# Schematic_Alarm_tone.net
KiCad netlist of a schematic drawn in Altium Designer
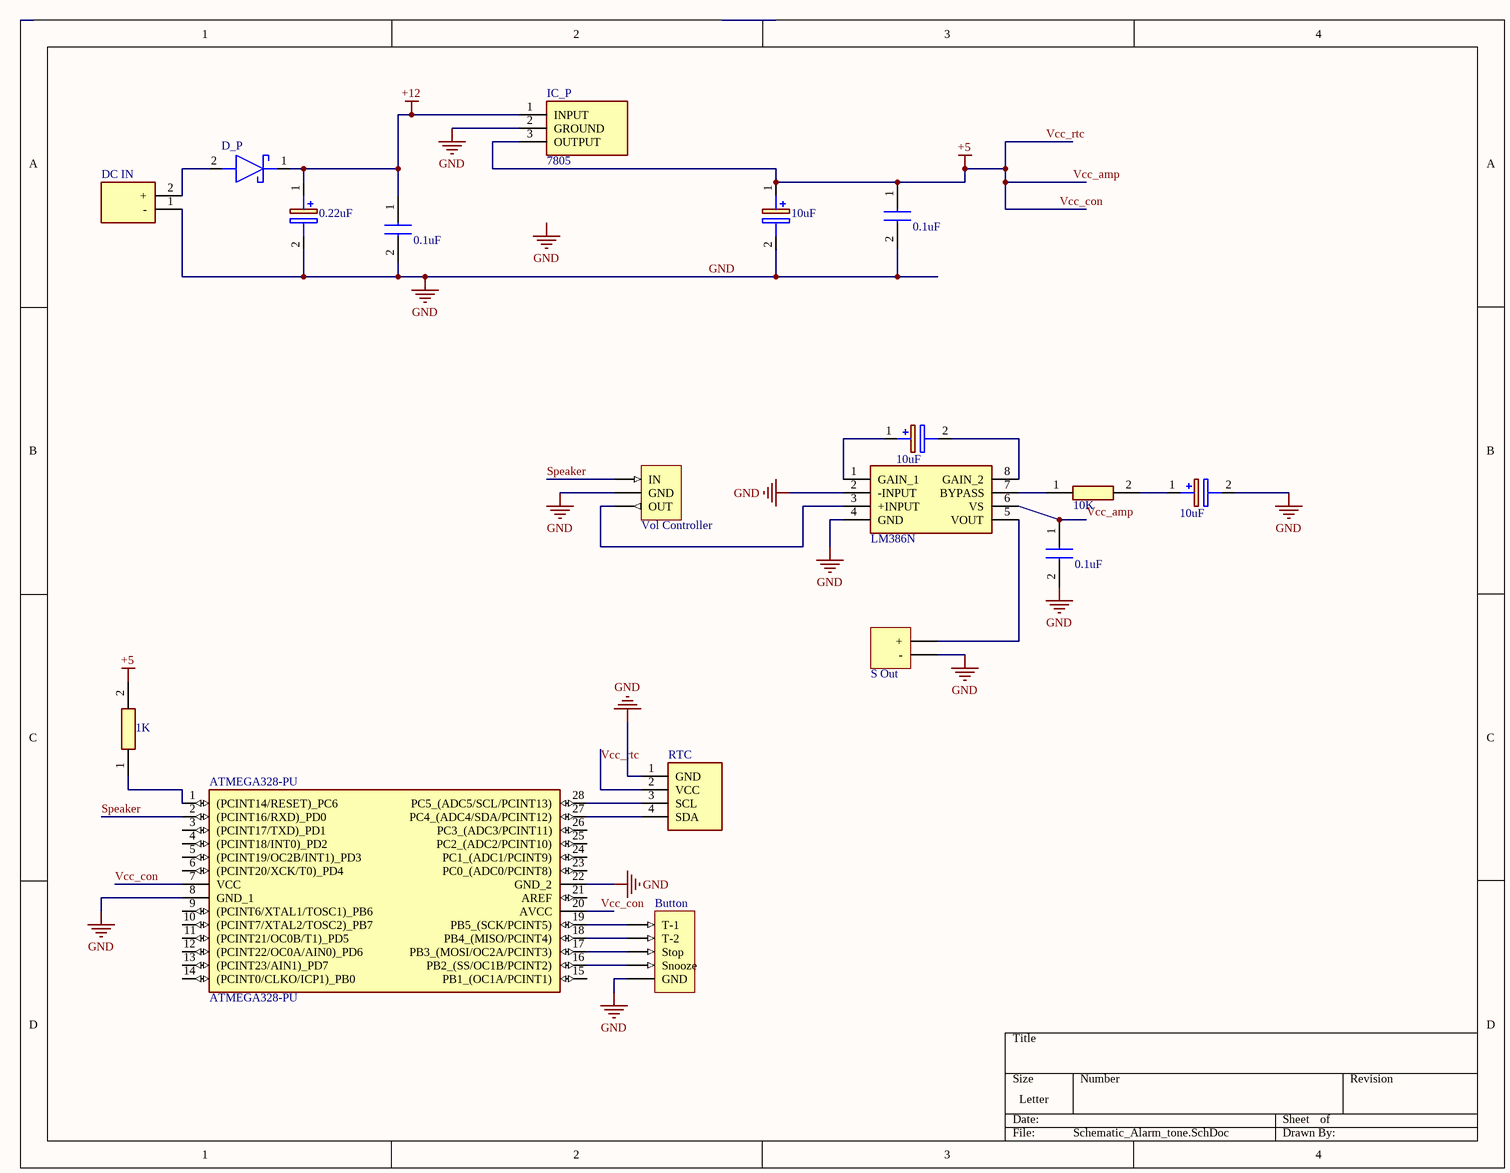
[diagram p0: Schematic_Alarm_tone.SchDoc]

(export (version "E")
  (design (tool "Eeschema 10.0.6"))
  (components
    (comp (ref "ATMEGA328-PU")
      (value "ATMEGA328-PU")
      (footprint "SamacSys:DIP1016W53P254L3468H457Q28N")
      (description "Integrated Circuit")
      (fields (field (name "MOUSER PART NUMBER") "556-ATMEGA328-PU"))
      (libsource (lib "*") (part "ATMEGA328-PU"))
    )
    (comp (ref "Button")
      (value "Header 5")
      (footprint "HDR1X5")
      (description "Header, 5-Pin")
      (fields (field (name "PUBLISHER") "Altium Limited"))
      (libsource (lib "Miscellaneous Connectors") (part "Header 5"))
    )
    (comp (ref "C1_A")
      (value "0.1uF")
      (footprint "SamacSys:RCE5C1H103J1A2H03B")
      (description "Capacitor")
      (fields (field (name "MANUFACTURER_PART_NUMBER") "RDER71E104K0K1H03B"))
      (libsource (lib "*") (part "RDER71E104K0K1H03B"))
    )
    (comp (ref "C1_P")
      (value "0.22uF")
      (footprint "SamacSys:CAPPRD200W52D500H1250")
      (description "Capacitor Polarised")
      (fields (field (name "MANUFACTURER_PART_NUMBER") "860010772002"))
      (libsource (lib "*") (part "860010772002"))
    )
    (comp (ref "C2_A")
      (value "10uF")
      (footprint "SamacSys:CAPPRD200W55D500H1250")
      (description "Capacitor Polarised")
      (fields
        (field (name "MOUSER2 PART NUMBER") "667-EEU-FR1H100")
        (field (name "MANUFACTURER_PART_NUMBER") "EEU-FR1H100")
      )
      (libsource (lib "") (part "EEU-FR1H100_1"))
    )
    (comp (ref "C2_P")
      (value "0.1uF")
      (footprint "SamacSys:RCE5C1H103J1A2H03B")
      (description "Capacitor")
      (fields (field (name "MANUFACTURER_PART_NUMBER") "RDER71E104K0K1H03B"))
      (libsource (lib "*") (part "RDER71E104K0K1H03B"))
    )
    (comp (ref "C3_A")
      (value "10uF")
      (footprint "SamacSys:CAPPRD200W55D500H1250")
      (description "Capacitor Polarised")
      (fields
        (field (name "MOUSER2 PART NUMBER") "667-EEU-FR1H100")
        (field (name "MANUFACTURER_PART_NUMBER") "EEU-FR1H100")
      )
      (libsource (lib "") (part "EEU-FR1H100_1"))
    )
    (comp (ref "C3_P")
      (value "10uF")
      (footprint "SamacSys:CAPPRD200W55D500H1250")
      (description "Capacitor Polarised")
      (fields
        (field (name "MOUSER2 PART NUMBER") "667-EEU-FR1H100")
        (field (name "MANUFACTURER_PART_NUMBER") "EEU-FR1H100")
      )
      (libsource (lib "*") (part "EEU-FR1H100"))
    )
    (comp (ref "C4_P")
      (value "0.1uF")
      (footprint "SamacSys:RCE5C1H103J1A2H03B")
      (description "Capacitor")
      (fields (field (name "MANUFACTURER_PART_NUMBER") "RDER71E104K0K1H03B"))
      (libsource (lib "*") (part "RDER71E104K0K1H03B"))
    )
    (comp (ref "DC IN")
      (value "0010845020")
      (footprint "SamacSys:0010845020")
      (description "Connector")
      (libsource (lib "*") (part "0010845020"))
    )
    (comp (ref "D_P")
      (value "SD103A-TR")
      (footprint "SamacSys:DIOAD950W60L350D150")
      (description "Schottky Diode")
      (fields (field (name "MOUSER2 PART NUMBER") "625-SD103A"))
      (libsource (lib "*") (part "SD103A-TR"))
    )
    (comp (ref "H4")
      (value "Vol Controller")
      (footprint "HDR1X3")
      (description "Header, 3-Pin")
      (fields (field (name "PUBLISHER") "Altium Limited"))
      (libsource (lib "Miscellaneous Connectors") (part "Header 3"))
    )
    (comp (ref "H5")
      (value "S Out")
      (footprint "HDR1X2")
      (description "Header, 2-Pin")
      (fields (field (name "PUBLISHER") "Altium Limited"))
      (libsource (lib "Miscellaneous Connectors") (part "Header 2"))
    )
    (comp (ref "IC")
      (value "LM386N")
      (footprint "SamacSys:DIP787W53P254L982H508Q8N")
      (description "Integrated Circuit")
      (fields
        (field (name "MANUFACTURER_PART_NUMBER") "LM386N-4")
        (field (name "MOUSER PART NUMBER") "926-LM386N-4")
      )
      (libsource (lib "*") (part "LM386N-4"))
    )
    (comp (ref "IC_P")
      (value "7805")
      (footprint "SamacSys:TO254P482X997X2018-3P")
      (description "Integrated Circuit")
      (fields
        (field (name "MANUFACTURER_PART_NUMBER") "MC7805CTG")
        (field (name "MOUSER PART NUMBER") "863-MC7805CTG")
      )
      (libsource (lib "*") (part "MC7805CTG"))
    )
    (comp (ref "R1_amp")
      (value "10K")
      (footprint "SamacSys:RESAD1650W60L650D250")
      (description "Resistor")
      (fields
        (field (name "MANUFACTURER_PART_NUMBER") "MRS25000C1002FRP00")
        (field (name "MOUSER PART NUMBER") "594-MRS2510K00F")
      )
      (libsource (lib "*") (part "MRS25000C1002FRP00"))
    )
    (comp (ref "R1_reset")
      (value "1K")
      (footprint "SamacSys:RESAD1680W59L680D250")
      (description "Resistor")
      (fields (field (name "MANUFACTURER_PART_NUMBER") "MF25 1K2"))
      (libsource (lib "*") (part "MF25_1K2"))
    )
    (comp (ref "RTC")
      (value "0022032041")
      (footprint "SamacSys:HDRV4W87P0X254_1X4_991X236X1155P")
      (description "Connector")
      (libsource (lib "*") (part "0022032041"))
    )
  )
  (nets
    (net (code "1") (name "+5") (class "Default")
      (node (ref "ATMEGA328-PU") (pin "20") (pinfunction "AVCC_20") (pintype "power_in"))
      (node (ref "ATMEGA328-PU") (pin "7") (pinfunction "VCC_7") (pintype "power_in"))
      (node (ref "C1_A") (pin "1") (pinfunction "1_1") (pintype "passive"))
      (node (ref "C3_P") (pin "1") (pinfunction "+_1") (pintype "power_in"))
      (node (ref "C4_P") (pin "1") (pinfunction "1_1") (pintype "passive"))
      (node (ref "IC") (pin "6") (pinfunction "VS_6") (pintype "passive"))
      (node (ref "IC_P") (pin "3") (pinfunction "OUTPUT_3") (pintype "power_in"))
      (node (ref "R1_reset") (pin "2") (pinfunction "2_2") (pintype "passive"))
      (node (ref "RTC") (pin "2") (pinfunction "VCC_2") (pintype "passive"))
    )
    (net (code "2") (name "+12") (class "Default")
      (node (ref "C1_P") (pin "1") (pinfunction "+_1") (pintype "passive"))
      (node (ref "C2_P") (pin "1") (pinfunction "1_1") (pintype "passive"))
      (node (ref "D_P") (pin "1") (pinfunction "K_1") (pintype "passive"))
      (node (ref "IC_P") (pin "1") (pinfunction "INPUT_1") (pintype "power_in"))
    )
    (net (code "4") (name "/Speaker") (class "Default")
      (node (ref "ATMEGA328-PU") (pin "2") (pinfunction "(PCINT16/RXD)_PD0_2") (pintype "bidirectional"))
      (node (ref "H4") (pin "1") (pinfunction "IN_1") (pintype "input"))
    )
    (net (code "5") (name "GND") (class "Default")
      (node (ref "ATMEGA328-PU") (pin "22") (pinfunction "GND_2_22") (pintype "power_in"))
      (node (ref "ATMEGA328-PU") (pin "8") (pinfunction "GND_1_8") (pintype "power_in"))
      (node (ref "Button") (pin "5") (pinfunction "GND_5") (pintype "power_in"))
      (node (ref "C1_A") (pin "2") (pinfunction "2_2") (pintype "passive"))
      (node (ref "C1_P") (pin "2") (pinfunction "-_2") (pintype "passive"))
      (node (ref "C2_P") (pin "2") (pinfunction "2_2") (pintype "passive"))
      (node (ref "C3_A") (pin "2") (pinfunction "-_2") (pintype "power_in"))
      (node (ref "C3_P") (pin "2") (pinfunction "-_2") (pintype "power_in"))
      (node (ref "C4_P") (pin "2") (pinfunction "2_2") (pintype "passive"))
      (node (ref "DC IN") (pin "1") (pinfunction "-_1") (pintype "power_in"))
      (node (ref "H4") (pin "2") (pinfunction "GND_2") (pintype "power_in"))
      (node (ref "H5") (pin "1") (pinfunction "-_1") (pintype "passive"))
      (node (ref "IC") (pin "2") (pinfunction "-INPUT_2") (pintype "passive"))
      (node (ref "IC") (pin "4") (pinfunction "GND_4") (pintype "passive"))
      (node (ref "IC_P") (pin "2") (pinfunction "GROUND_2") (pintype "power_in"))
      (node (ref "RTC") (pin "1") (pinfunction "GND_1") (pintype "passive"))
    )
    (net (code "6") (name "Net-(ATMEGA328-PU-(PCINT14{slash}RESET)_PC6)") (class "Default")
      (node (ref "ATMEGA328-PU") (pin "1") (pinfunction "(PCINT14/RESET)_PC6_1") (pintype "bidirectional"))
      (node (ref "R1_reset") (pin "1") (pinfunction "1_1") (pintype "passive"))
    )
    (net (code "7") (name "Net-(ATMEGA328-PU-PB2_(SS{slash}OC1B{slash}PCINT2))") (class "Default")
      (node (ref "ATMEGA328-PU") (pin "16") (pinfunction "PB2_(SS/OC1B/PCINT2)_16") (pintype "bidirectional"))
      (node (ref "Button") (pin "4") (pinfunction "Snooze_4") (pintype "input"))
    )
    (net (code "8") (name "Net-(ATMEGA328-PU-PB3_(MOSI{slash}OC2A{slash}PCINT3))") (class "Default")
      (node (ref "ATMEGA328-PU") (pin "17") (pinfunction "PB3_(MOSI/OC2A/PCINT3)_17") (pintype "bidirectional"))
      (node (ref "Button") (pin "3") (pinfunction "Stop_3") (pintype "input"))
    )
    (net (code "9") (name "Net-(ATMEGA328-PU-PB4_(MISO{slash}PCINT4))") (class "Default")
      (node (ref "ATMEGA328-PU") (pin "18") (pinfunction "PB4_(MISO/PCINT4)_18") (pintype "bidirectional"))
      (node (ref "Button") (pin "2") (pinfunction "T-2_2") (pintype "input"))
    )
    (net (code "10") (name "Net-(ATMEGA328-PU-PB5_(SCK{slash}PCINT5))") (class "Default")
      (node (ref "ATMEGA328-PU") (pin "19") (pinfunction "PB5_(SCK/PCINT5)_19") (pintype "bidirectional"))
      (node (ref "Button") (pin "1") (pinfunction "T-1_1") (pintype "input"))
    )
    (net (code "11") (name "Net-(ATMEGA328-PU-PC4_(ADC4{slash}SDA{slash}PCINT12))") (class "Default")
      (node (ref "ATMEGA328-PU") (pin "27") (pinfunction "PC4_(ADC4/SDA/PCINT12)_27") (pintype "bidirectional"))
      (node (ref "RTC") (pin "4") (pinfunction "SDA_4") (pintype "passive"))
    )
    (net (code "12") (name "Net-(ATMEGA328-PU-PC5_(ADC5{slash}SCL{slash}PCINT13))") (class "Default")
      (node (ref "ATMEGA328-PU") (pin "28") (pinfunction "PC5_(ADC5/SCL/PCINT13)_28") (pintype "bidirectional"))
      (node (ref "RTC") (pin "3") (pinfunction "SCL_3") (pintype "passive"))
    )
    (net (code "13") (name "Net-(C2_A-+)") (class "Default")
      (node (ref "C2_A") (pin "1") (pinfunction "+_1") (pintype "power_in"))
      (node (ref "IC") (pin "1") (pinfunction "GAIN_1_1") (pintype "passive"))
    )
    (net (code "14") (name "Net-(C2_A--)") (class "Default")
      (node (ref "C2_A") (pin "2") (pinfunction "-_2") (pintype "power_in"))
      (node (ref "IC") (pin "8") (pinfunction "GAIN_2_8") (pintype "passive"))
    )
    (net (code "15") (name "Net-(C3_A-+)") (class "Default")
      (node (ref "C3_A") (pin "1") (pinfunction "+_1") (pintype "power_in"))
      (node (ref "R1_amp") (pin "2") (pinfunction "2_2") (pintype "passive"))
    )
    (net (code "16") (name "Net-(DC IN-+)") (class "Default")
      (node (ref "DC IN") (pin "2") (pinfunction "+_2") (pintype "power_in"))
      (node (ref "D_P") (pin "2") (pinfunction "A_2") (pintype "passive"))
    )
    (net (code "17") (name "Net-(H4-OUT)") (class "Default")
      (node (ref "H4") (pin "3") (pinfunction "OUT_3") (pintype "output"))
      (node (ref "IC") (pin "3") (pinfunction "+INPUT_3") (pintype "passive"))
    )
    (net (code "18") (name "Net-(H5-+)") (class "Default")
      (node (ref "H5") (pin "2") (pinfunction "+_2") (pintype "passive"))
      (node (ref "IC") (pin "5") (pinfunction "VOUT_5") (pintype "passive"))
    )
    (net (code "19") (name "Net-(IC-BYPASS)") (class "Default")
      (node (ref "IC") (pin "7") (pinfunction "BYPASS_7") (pintype "passive"))
      (node (ref "R1_amp") (pin "1") (pinfunction "1_1") (pintype "passive"))
    )
    (net (code "20") (name "unconnected-(ATMEGA328-PU-(PCINT0{slash}CLKO{slash}ICP1)_PB0-Pad14)") (class "Default")
      (node (ref "ATMEGA328-PU") (pin "14") (pinfunction "(PCINT0/CLKO/ICP1)_PB0_14") (pintype "bidirectional"))
    )
    (net (code "21") (name "unconnected-(ATMEGA328-PU-(PCINT6{slash}XTAL1{slash}TOSC1)_PB6-Pad9)") (class "Default")
      (node (ref "ATMEGA328-PU") (pin "9") (pinfunction "(PCINT6/XTAL1/TOSC1)_PB6_9") (pintype "bidirectional"))
    )
    (net (code "22") (name "unconnected-(ATMEGA328-PU-(PCINT7{slash}XTAL2{slash}TOSC2)_PB7-Pad10)") (class "Default")
      (node (ref "ATMEGA328-PU") (pin "10") (pinfunction "(PCINT7/XTAL2/TOSC2)_PB7_10") (pintype "bidirectional"))
    )
    (net (code "23") (name "unconnected-(ATMEGA328-PU-(PCINT17{slash}TXD)_PD1-Pad3)") (class "Default")
      (node (ref "ATMEGA328-PU") (pin "3") (pinfunction "(PCINT17/TXD)_PD1_3") (pintype "bidirectional"))
    )
    (net (code "24") (name "unconnected-(ATMEGA328-PU-(PCINT18{slash}INT0)_PD2-Pad4)") (class "Default")
      (node (ref "ATMEGA328-PU") (pin "4") (pinfunction "(PCINT18/INT0)_PD2_4") (pintype "bidirectional"))
    )
    (net (code "25") (name "unconnected-(ATMEGA328-PU-(PCINT19{slash}OC2B{slash}INT1)_PD3-Pad5)") (class "Default")
      (node (ref "ATMEGA328-PU") (pin "5") (pinfunction "(PCINT19/OC2B/INT1)_PD3_5") (pintype "bidirectional"))
    )
    (net (code "26") (name "unconnected-(ATMEGA328-PU-(PCINT20{slash}XCK{slash}T0)_PD4-Pad6)") (class "Default")
      (node (ref "ATMEGA328-PU") (pin "6") (pinfunction "(PCINT20/XCK/T0)_PD4_6") (pintype "bidirectional"))
    )
    (net (code "27") (name "unconnected-(ATMEGA328-PU-(PCINT21{slash}OC0B{slash}T1)_PD5-Pad11)") (class "Default")
      (node (ref "ATMEGA328-PU") (pin "11") (pinfunction "(PCINT21/OC0B/T1)_PD5_11") (pintype "bidirectional"))
    )
    (net (code "28") (name "unconnected-(ATMEGA328-PU-(PCINT22{slash}OC0A{slash}AIN0)_PD6-Pad12)") (class "Default")
      (node (ref "ATMEGA328-PU") (pin "12") (pinfunction "(PCINT22/OC0A/AIN0)_PD6_12") (pintype "bidirectional"))
    )
    (net (code "29") (name "unconnected-(ATMEGA328-PU-(PCINT23{slash}AIN1)_PD7-Pad13)") (class "Default")
      (node (ref "ATMEGA328-PU") (pin "13") (pinfunction "(PCINT23/AIN1)_PD7_13") (pintype "bidirectional"))
    )
    (net (code "30") (name "unconnected-(ATMEGA328-PU-AREF-Pad21)") (class "Default")
      (node (ref "ATMEGA328-PU") (pin "21") (pinfunction "AREF_21") (pintype "bidirectional"))
    )
    (net (code "31") (name "unconnected-(ATMEGA328-PU-PB1_(OC1A{slash}PCINT1)-Pad15)") (class "Default")
      (node (ref "ATMEGA328-PU") (pin "15") (pinfunction "PB1_(OC1A/PCINT1)_15") (pintype "bidirectional"))
    )
    (net (code "32") (name "unconnected-(ATMEGA328-PU-PC0_(ADC0{slash}PCINT8)-Pad23)") (class "Default")
      (node (ref "ATMEGA328-PU") (pin "23") (pinfunction "PC0_(ADC0/PCINT8)_23") (pintype "bidirectional"))
    )
    (net (code "33") (name "unconnected-(ATMEGA328-PU-PC1_(ADC1{slash}PCINT9)-Pad24)") (class "Default")
      (node (ref "ATMEGA328-PU") (pin "24") (pinfunction "PC1_(ADC1/PCINT9)_24") (pintype "bidirectional"))
    )
    (net (code "34") (name "unconnected-(ATMEGA328-PU-PC2_(ADC2{slash}PCINT10)-Pad25)") (class "Default")
      (node (ref "ATMEGA328-PU") (pin "25") (pinfunction "PC2_(ADC2/PCINT10)_25") (pintype "bidirectional"))
    )
    (net (code "35") (name "unconnected-(ATMEGA328-PU-PC3_(ADC3{slash}PCINT11)-Pad26)") (class "Default")
      (node (ref "ATMEGA328-PU") (pin "26") (pinfunction "PC3_(ADC3/PCINT11)_26") (pintype "bidirectional"))
    )
  )
)
